# SCH_555-Circuit_2025-03-19.net
KiCad netlist of a schematic drawn in EasyEDA
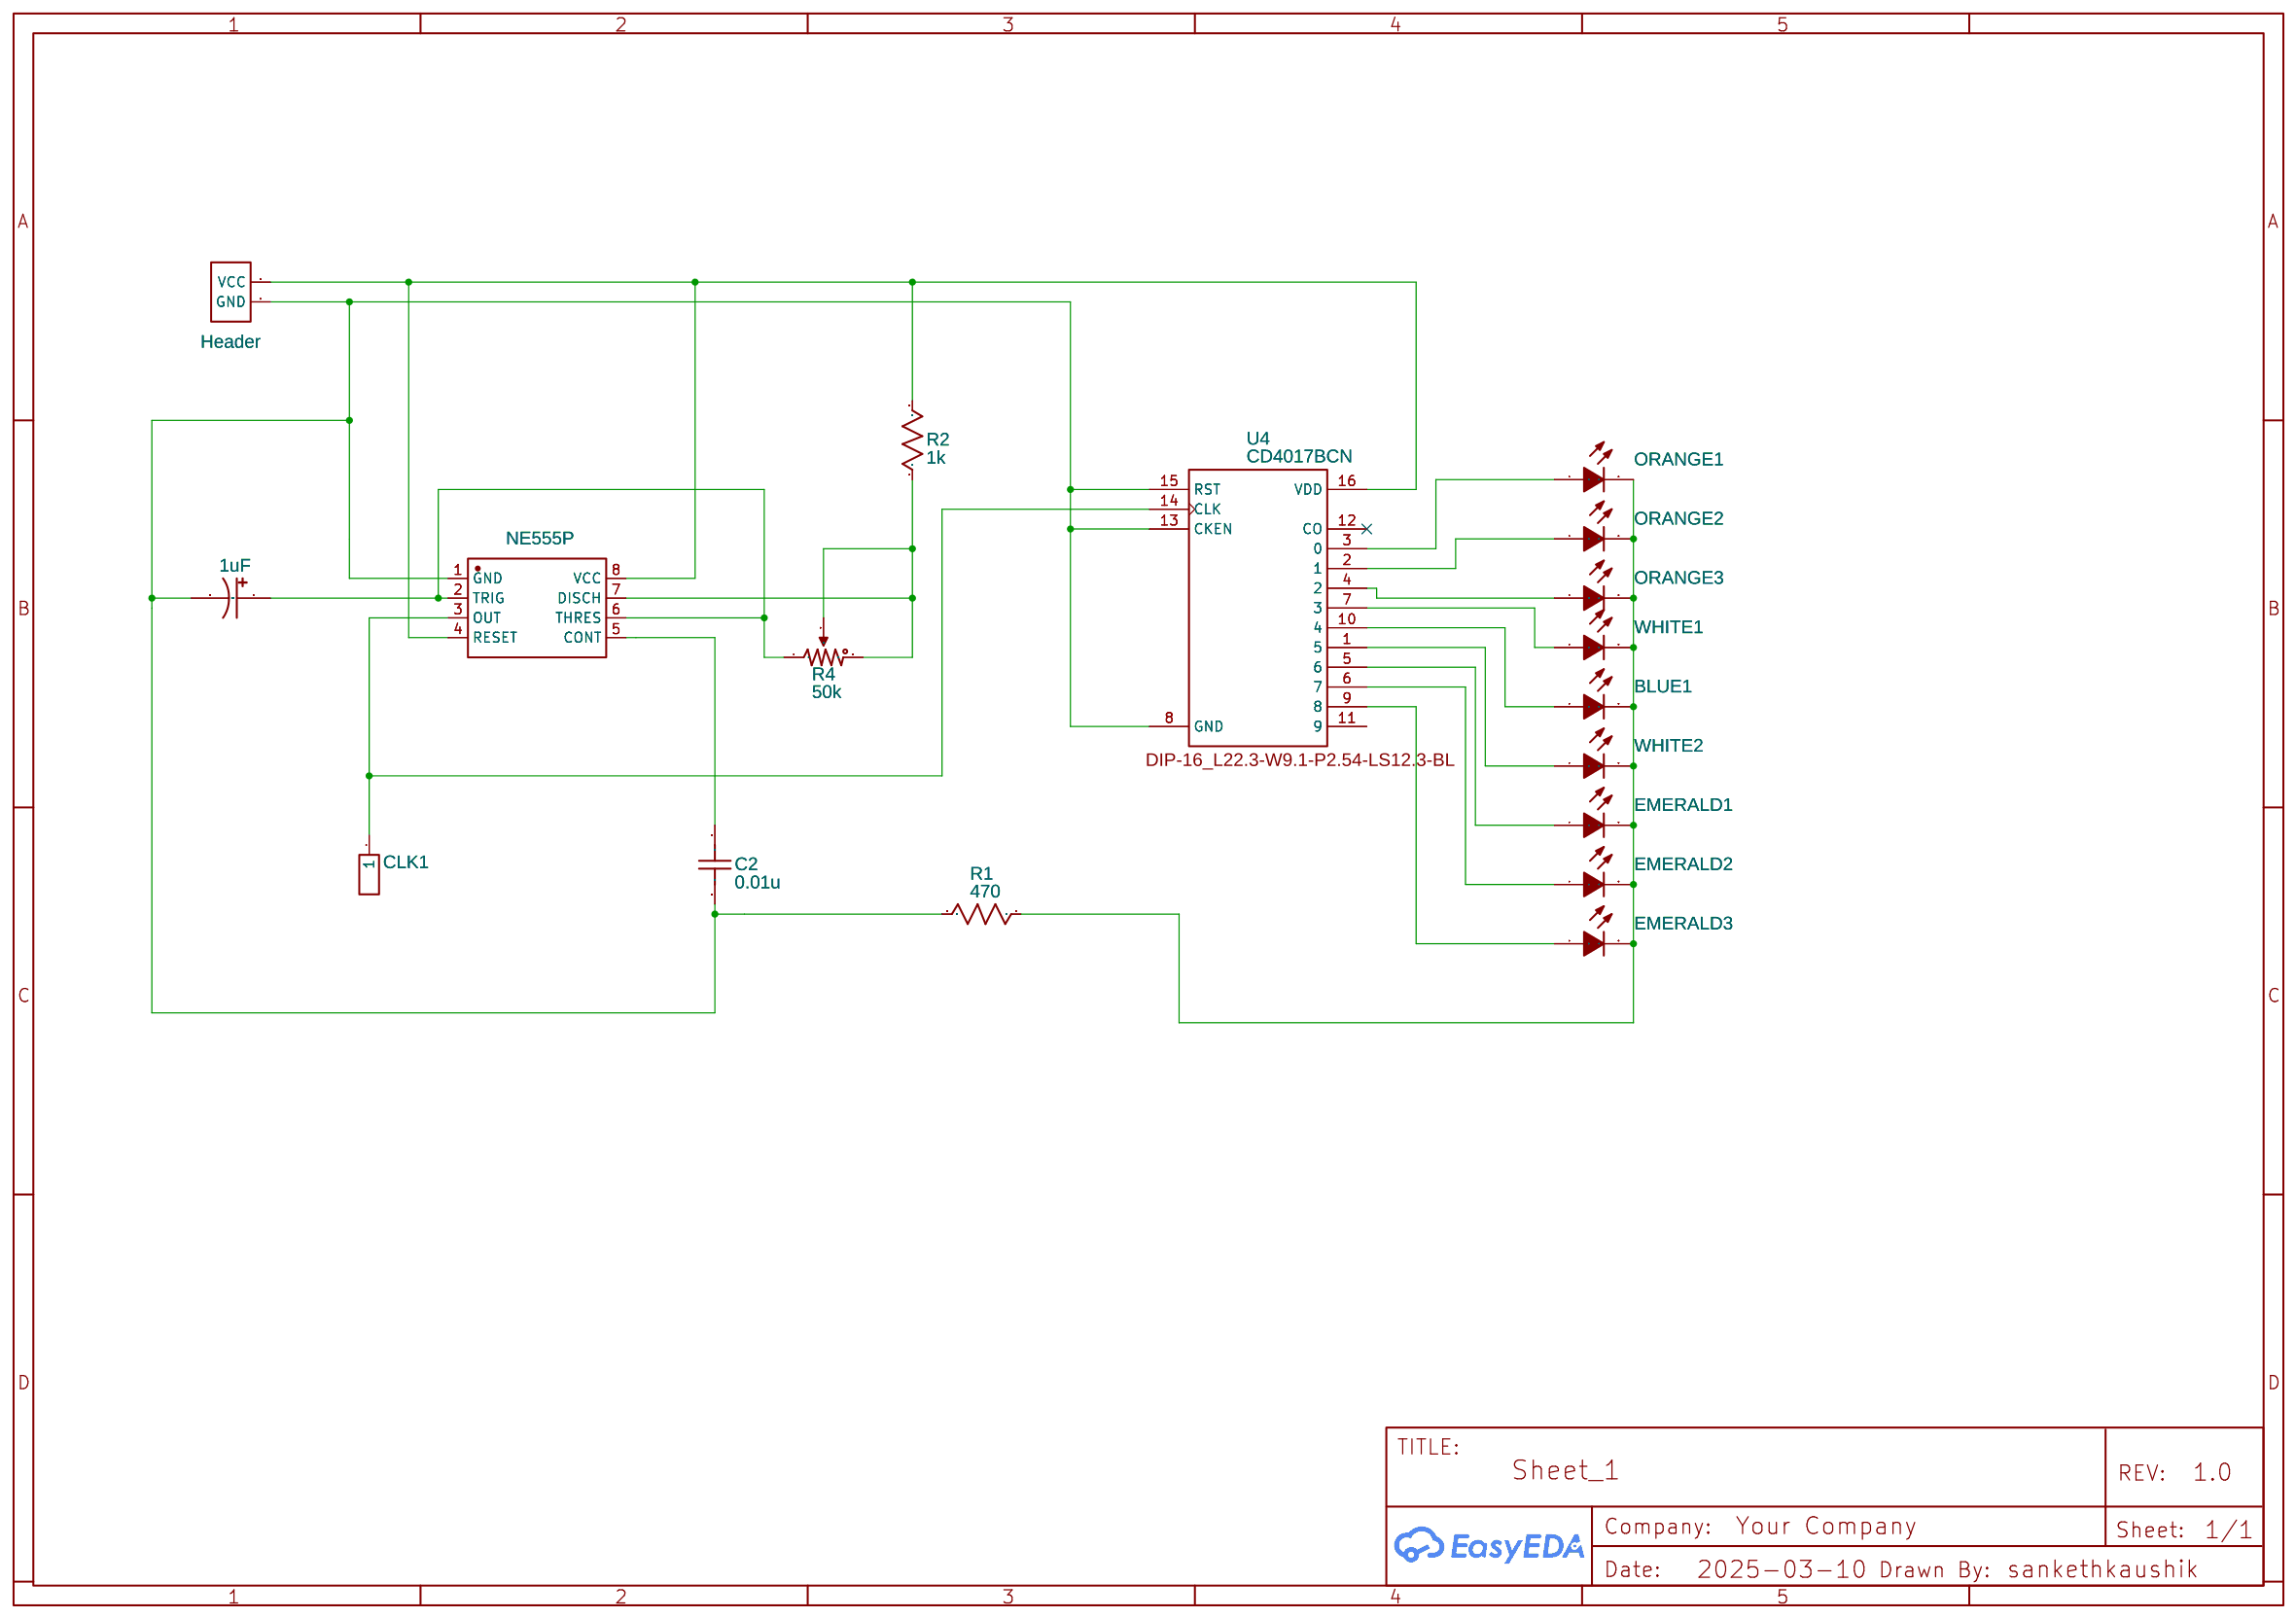
[diagram p0: schematic sheet]

(export (version "E")
  (design (tool "Eeschema 10.0.6"))
  (components
    (comp (ref "BLUE1") (value "LED_5MM") (libsource (lib "") (part "LED_5MM_3")))
    (comp (ref "C1")
      (value "1uF")
      (fields (field (name "Manufacturer Part") "UVZ1H010MDD") (field (name "Manufacturer") "Nichicon(尼吉康)"))
      (libsource (lib "") (part "UVZ1H010MDD"))
    )
    (comp (ref "C2") (value "0.01u") (libsource (lib "") (part "C_0603_US")))
    (comp (ref "CLK1")
      (value "C81276")
      (fields
        (field (name "Manufacturer Part") "2.54-1*1P针")
        (field (name "Manufacturer") "BOOMELE(Boom Precision Elec)")
      )
      (libsource (lib "") (part "Header-Male-2.54_1x1"))
    )
    (comp (ref "EMERALD1") (value "LED_5MM") (libsource (lib "") (part "LED_5MM")))
    (comp (ref "EMERALD2") (value "LED_5MM") (libsource (lib "") (part "LED_5MM")))
    (comp (ref "EMERALD3") (value "LED_5MM") (libsource (lib "") (part "LED_5MM")))
    (comp (ref "H1") (value "Header") (libsource (lib "") (part "HEADER-FEMALE-2.54_1X2")))
    (comp (ref "ORANGE1") (value "LED_5MM") (libsource (lib "") (part "LED_5MM_2")))
    (comp (ref "ORANGE2") (value "LED_5MM") (libsource (lib "") (part "LED_5MM_2")))
    (comp (ref "ORANGE3") (value "LED_5MM") (libsource (lib "") (part "LED_5MM_2")))
    (comp (ref "R1")
      (value "470")
      (fields (field (name "Manufacturer Part") "?"))
      (libsource (lib "") (part "Resistor_1"))
    )
    (comp (ref "R2")
      (value "1k")
      (fields (field (name "Manufacturer Part") "?"))
      (libsource (lib "") (part "Resistor"))
    )
    (comp (ref "R4")
      (value "50k")
      (fields (field (name "Manufacturer Part") "?"))
      (libsource (lib "") (part "Potentiometer"))
    )
    (comp (ref "U2")
      (value "NE555P")
      (fields (field (name "Manufacturer") "TI(德州仪器)"))
      (libsource (lib "") (part "NE555P"))
    )
    (comp (ref "U4") (value "CD4017BCN") (libsource (lib "") (part "CD4017BCN")))
    (comp (ref "WHITE1") (value "LED_5MM") (libsource (lib "") (part "LED_5MM_1")))
    (comp (ref "WHITE2") (value "LED_5MM") (libsource (lib "") (part "LED_5MM_1")))
  )
  (nets
    (net (code "1") (name "Net-(BLUE1-A)") (class "Default")
      (node (ref "BLUE1") (pin "1") (pinfunction "A_1") (pintype "input"))
      (node (ref "U4") (pin "10") (pinfunction "4_10") (pintype "output"))
    )
    (net (code "2") (name "Net-(BLUE1-K)") (class "Default")
      (node (ref "BLUE1") (pin "2") (pinfunction "K_2") (pintype "input"))
      (node (ref "EMERALD1") (pin "2") (pinfunction "K_2") (pintype "input"))
      (node (ref "EMERALD2") (pin "2") (pinfunction "K_2") (pintype "input"))
      (node (ref "EMERALD3") (pin "2") (pinfunction "K_2") (pintype "input"))
      (node (ref "ORANGE1") (pin "2") (pinfunction "K_2") (pintype "input"))
      (node (ref "ORANGE2") (pin "2") (pinfunction "K_2") (pintype "input"))
      (node (ref "ORANGE3") (pin "2") (pinfunction "K_2") (pintype "input"))
      (node (ref "R1") (pin "1") (pinfunction "1_1") (pintype "unspecified"))
      (node (ref "WHITE1") (pin "2") (pinfunction "K_2") (pintype "input"))
      (node (ref "WHITE2") (pin "2") (pinfunction "K_2") (pintype "input"))
    )
    (net (code "3") (name "Net-(EMERALD1-A)") (class "Default")
      (node (ref "EMERALD1") (pin "1") (pinfunction "A_1") (pintype "input"))
      (node (ref "U4") (pin "5") (pinfunction "6_5") (pintype "output"))
    )
    (net (code "4") (name "Net-(EMERALD2-A)") (class "Default")
      (node (ref "EMERALD2") (pin "1") (pinfunction "A_1") (pintype "input"))
      (node (ref "U4") (pin "6") (pinfunction "7_6") (pintype "output"))
    )
    (net (code "5") (name "Net-(EMERALD3-A)") (class "Default")
      (node (ref "EMERALD3") (pin "1") (pinfunction "A_1") (pintype "input"))
      (node (ref "U4") (pin "9") (pinfunction "8_9") (pintype "output"))
    )
    (net (code "6") (name "Net-(H1-GND)") (class "Default")
      (node (ref "C1") (pin "2") (pinfunction "2_2") (pintype "unspecified"))
      (node (ref "C2") (pin "2") (pinfunction "2_2") (pintype "unspecified"))
      (node (ref "H1") (pin "2") (pinfunction "GND_2") (pintype "unspecified"))
      (node (ref "R1") (pin "2") (pinfunction "2_2") (pintype "unspecified"))
      (node (ref "U2") (pin "1") (pinfunction "GND_1") (pintype "unspecified"))
      (node (ref "U4") (pin "13") (pinfunction "CKEN_13") (pintype "unspecified"))
      (node (ref "U4") (pin "15") (pinfunction "RST_15") (pintype "unspecified"))
      (node (ref "U4") (pin "8") (pinfunction "GND_8") (pintype "passive"))
    )
    (net (code "7") (name "Net-(H1-VCC)") (class "Default")
      (node (ref "H1") (pin "1") (pinfunction "VCC_1") (pintype "unspecified"))
      (node (ref "R2") (pin "2") (pinfunction "2_2") (pintype "unspecified"))
      (node (ref "U2") (pin "4") (pinfunction "RESET_4") (pintype "unspecified"))
      (node (ref "U2") (pin "8") (pinfunction "VCC_8") (pintype "unspecified"))
      (node (ref "U4") (pin "16") (pinfunction "VDD_16") (pintype "passive"))
    )
    (net (code "8") (name "Net-(ORANGE1-A)") (class "Default")
      (node (ref "ORANGE1") (pin "1") (pinfunction "A_1") (pintype "input"))
      (node (ref "U4") (pin "3") (pinfunction "0_3") (pintype "output"))
    )
    (net (code "9") (name "Net-(ORANGE2-A)") (class "Default")
      (node (ref "ORANGE2") (pin "1") (pinfunction "A_1") (pintype "input"))
      (node (ref "U4") (pin "2") (pinfunction "1_2") (pintype "output"))
    )
    (net (code "10") (name "Net-(ORANGE3-A)") (class "Default")
      (node (ref "ORANGE3") (pin "1") (pinfunction "A_1") (pintype "input"))
      (node (ref "U4") (pin "4") (pinfunction "2_4") (pintype "output"))
    )
    (net (code "11") (name "Net-(R4-2)") (class "Default")
      (node (ref "R2") (pin "1") (pinfunction "1_1") (pintype "unspecified"))
      (node (ref "R4") (pin "2") (pinfunction "3_2") (pintype "unspecified"))
      (node (ref "R4") (pin "3") (pinfunction "2_3") (pintype "unspecified"))
      (node (ref "U2") (pin "7") (pinfunction "DISCH_7") (pintype "unspecified"))
    )
    (net (code "12") (name "Net-(U2-CONT)") (class "Default")
      (node (ref "C2") (pin "1") (pinfunction "1_1") (pintype "unspecified"))
      (node (ref "U2") (pin "5") (pinfunction "CONT_5") (pintype "unspecified"))
    )
    (net (code "13") (name "Net-(U2-OUT)") (class "Default")
      (node (ref "CLK1") (pin "1") (pinfunction "1_1") (pintype "unspecified"))
      (node (ref "U2") (pin "3") (pinfunction "OUT_3") (pintype "unspecified"))
      (node (ref "U4") (pin "14") (pinfunction "CLK_14") (pintype "unspecified"))
    )
    (net (code "14") (name "Net-(U2-THRES)") (class "Default")
      (node (ref "C1") (pin "1") (pinfunction "1_1") (pintype "unspecified"))
      (node (ref "R4") (pin "1") (pinfunction "1_1") (pintype "unspecified"))
      (node (ref "U2") (pin "2") (pinfunction "TRIG_2") (pintype "unspecified"))
      (node (ref "U2") (pin "6") (pinfunction "THRES_6") (pintype "unspecified"))
    )
    (net (code "15") (name "Net-(U4-3)") (class "Default")
      (node (ref "U4") (pin "7") (pinfunction "3_7") (pintype "output"))
      (node (ref "WHITE1") (pin "1") (pinfunction "A_1") (pintype "input"))
    )
    (net (code "16") (name "Net-(U4-5)") (class "Default")
      (node (ref "U4") (pin "1") (pinfunction "5_1") (pintype "output"))
      (node (ref "WHITE2") (pin "1") (pinfunction "A_1") (pintype "input"))
    )
    (net (code "17") (name "unconnected-(U4-9-Pad11)") (class "Default")
      (node (ref "U4") (pin "11") (pinfunction "9_11") (pintype "output"))
    )
    (net (code "18") (name "unconnected-(U4-CO-Pad12)") (class "Default")
      (node (ref "U4") (pin "12") (pinfunction "CO_12") (pintype "output+no_connect"))
    )
  )
)
